# dubBoard.net
KiCad netlist of a schematic drawn in EAGLE
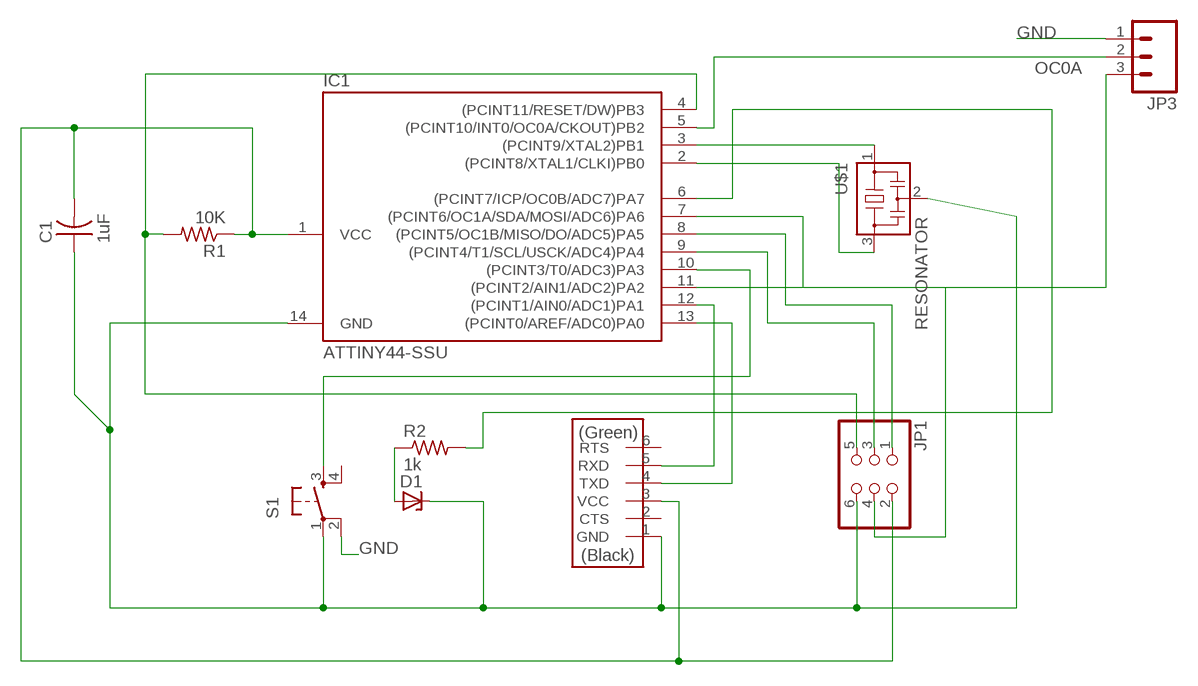
[diagram p0: schematic, sheet 1]

(export (version "E")
  (design (tool "Eeschema 10.0.6"))
  (components
    (comp (ref "C1")
      (value "1uF")
      (footprint "eagle-import:C1206FAB")
      (libsource (lib "eagle-import") (part "CAP-US1206FAB"))
    )
    (comp (ref "D1")
      (value "ZENER_DIODESOD123")
      (footprint "eagle-import:SOD123")
      (libsource (lib "eagle-import") (part "ZENER_DIODESOD123"))
    )
    (comp (ref "IC1")
      (value "ATTINY44-SSU")
      (footprint "eagle-import:SOIC14")
      (libsource (lib "eagle-import") (part "ATTINY44-SSU"))
    )
    (comp (ref "JP1")
      (value "PINHD-2X3-SMD")
      (footprint "eagle-import:2X03SMD")
      (libsource (lib "eagle-import") (part "PINHD-2X3-SMD"))
    )
    (comp (ref "JP3")
      (value "M03SMD_RA_MALE")
      (footprint "eagle-import:1X03_SMD_RA_MALE")
      (libsource (lib "eagle-import") (part "M03SMD_RA_MALE"))
    )
    (comp (ref "R1")
      (value "10K")
      (footprint "eagle-import:R1206")
      (libsource (lib "eagle-import") (part "RES-US1206"))
    )
    (comp (ref "R2")
      (value "1k")
      (footprint "eagle-import:R1206FAB")
      (libsource (lib "eagle-import") (part "RES-US1206FAB"))
    )
    (comp (ref "S1")
      (value "6MM_SWITCH6MM_SWITCH")
      (footprint "eagle-import:6MM_SWITCH")
      (libsource (lib "eagle-import") (part "6MM_SWITCH6MM_SWITCH"))
    )
    (comp (ref "U$1")
      (value "RESONATOR")
      (footprint "eagle-import:EFOBM")
      (libsource (lib "eagle-import") (part "RESONATOR"))
    )
    (comp (ref "U$2")
      (value "FTDI-SMD-HEADER")
      (footprint "eagle-import:1X06SMD")
      (libsource (lib "eagle-import") (part "FTDI-SMD-HEADER"))
    )
  )
  (nets
    (net (code "1") (name "/GND") (class "Default")
      (node (ref "C1") (pin "1") (pinfunction "1_1") (pintype "passive"))
      (node (ref "D1") (pin "CATHODE") (pinfunction "CATHODE_CATHODE") (pintype "passive"))
      (node (ref "IC1") (pin "14") (pinfunction "GND_14") (pintype "power_in"))
      (node (ref "JP1") (pin "6") (pinfunction "6_6") (pintype "passive"))
      (node (ref "JP3") (pin "1") (pinfunction "1_1") (pintype "passive"))
      (node (ref "S1") (pin "1") (pinfunction "P_1") (pintype "passive"))
      (node (ref "S1") (pin "2") (pinfunction "P1_2") (pintype "passive"))
      (node (ref "U$1") (pin "2") (pinfunction "2_2") (pintype "passive"))
      (node (ref "U$2") (pin "1") (pinfunction "GND_1") (pintype "bidirectional"))
    )
    (net (code "2") (name "/OC0A") (class "Default")
      (node (ref "IC1") (pin "5") (pinfunction "(PCINT10/INT0/OC0A/CKOUT)PB2_5") (pintype "bidirectional"))
      (node (ref "JP3") (pin "2") (pinfunction "2_2") (pintype "passive"))
    )
    (net (code "3") (name "Net-(D1-PadANODE)") (class "Default")
      (node (ref "D1") (pin "ANODE") (pinfunction "ANODE_ANODE") (pintype "passive"))
      (node (ref "R2") (pin "1") (pinfunction "1_1") (pintype "passive"))
    )
    (net (code "4") (name "Net-(IC1-(PCINT0{slash}AREF{slash}ADC0)PA0)") (class "Default")
      (node (ref "IC1") (pin "13") (pinfunction "(PCINT0/AREF/ADC0)PA0_13") (pintype "bidirectional"))
      (node (ref "U$2") (pin "4") (pinfunction "TXD_4") (pintype "bidirectional"))
    )
    (net (code "5") (name "Net-(IC1-(PCINT1{slash}AIN0{slash}ADC1)PA1)") (class "Default")
      (node (ref "IC1") (pin "12") (pinfunction "(PCINT1/AIN0/ADC1)PA1_12") (pintype "bidirectional"))
      (node (ref "U$2") (pin "5") (pinfunction "RXD_5") (pintype "bidirectional"))
    )
    (net (code "6") (name "Net-(IC1-(PCINT2{slash}AIN1{slash}ADC2)PA2)") (class "Default")
      (node (ref "IC1") (pin "11") (pinfunction "(PCINT2/AIN1/ADC2)PA2_11") (pintype "bidirectional"))
      (node (ref "JP3") (pin "3") (pinfunction "3_3") (pintype "passive"))
    )
    (net (code "7") (name "Net-(IC1-(PCINT3{slash}T0{slash}ADC3)PA3)") (class "Default")
      (node (ref "IC1") (pin "10") (pinfunction "(PCINT3/T0/ADC3)PA3_10") (pintype "bidirectional"))
      (node (ref "S1") (pin "3") (pinfunction "S_3") (pintype "passive"))
    )
    (net (code "8") (name "Net-(IC1-(PCINT4{slash}T1{slash}SCL{slash}USCK{slash}ADC4)PA4)") (class "Default")
      (node (ref "IC1") (pin "9") (pinfunction "(PCINT4/T1/SCL/USCK/ADC4)PA4_9") (pintype "bidirectional"))
      (node (ref "JP1") (pin "3") (pinfunction "3_3") (pintype "passive"))
    )
    (net (code "9") (name "Net-(IC1-(PCINT5{slash}OC1B{slash}MISO{slash}DO{slash}ADC5)PA5)") (class "Default")
      (node (ref "IC1") (pin "8") (pinfunction "(PCINT5/OC1B/MISO/DO/ADC5)PA5_8") (pintype "bidirectional"))
      (node (ref "JP1") (pin "1") (pinfunction "1_1") (pintype "passive"))
    )
    (net (code "10") (name "Net-(IC1-(PCINT6{slash}OC1A{slash}SDA{slash}MOSI{slash}ADC6)PA6)") (class "Default")
      (node (ref "IC1") (pin "7") (pinfunction "(PCINT6/OC1A/SDA/MOSI/ADC6)PA6_7") (pintype "bidirectional"))
      (node (ref "JP1") (pin "4") (pinfunction "4_4") (pintype "passive"))
    )
    (net (code "11") (name "Net-(IC1-(PCINT7{slash}ICP{slash}OC0B{slash}ADC7)PA7)") (class "Default")
      (node (ref "IC1") (pin "6") (pinfunction "(PCINT7/ICP/OC0B/ADC7)PA7_6") (pintype "bidirectional"))
      (node (ref "R2") (pin "2") (pinfunction "2_2") (pintype "passive"))
    )
    (net (code "12") (name "Net-(IC1-(PCINT8{slash}XTAL1{slash}CLKI)PB0)") (class "Default")
      (node (ref "IC1") (pin "2") (pinfunction "(PCINT8/XTAL1/CLKI)PB0_2") (pintype "bidirectional"))
      (node (ref "U$1") (pin "3") (pinfunction "3_3") (pintype "passive"))
    )
    (net (code "13") (name "Net-(IC1-(PCINT9{slash}XTAL2)PB1)") (class "Default")
      (node (ref "IC1") (pin "3") (pinfunction "(PCINT9/XTAL2)PB1_3") (pintype "bidirectional"))
      (node (ref "U$1") (pin "1") (pinfunction "1_1") (pintype "passive"))
    )
    (net (code "14") (name "Net-(IC1-(PCINT11{slash}RESET{slash}DW)PB3)") (class "Default")
      (node (ref "IC1") (pin "4") (pinfunction "(PCINT11/RESET/DW)PB3_4") (pintype "bidirectional"))
      (node (ref "JP1") (pin "5") (pinfunction "5_5") (pintype "passive"))
      (node (ref "R1") (pin "2") (pinfunction "2_2") (pintype "passive"))
    )
    (net (code "15") (name "Net-(IC1-VCC)") (class "Default")
      (node (ref "C1") (pin "2") (pinfunction "2_2") (pintype "passive"))
      (node (ref "IC1") (pin "1") (pinfunction "VCC_1") (pintype "power_in"))
      (node (ref "JP1") (pin "2") (pinfunction "2_2") (pintype "passive"))
      (node (ref "R1") (pin "1") (pinfunction "1_1") (pintype "passive"))
      (node (ref "U$2") (pin "3") (pinfunction "VCC_3") (pintype "bidirectional"))
    )
    (net (code "16") (name "unconnected-(S1-S1-Pad4)") (class "Default")
      (node (ref "S1") (pin "4") (pinfunction "S1_4") (pintype "passive"))
    )
    (net (code "17") (name "unconnected-(U$2-CTS-Pad2)") (class "Default")
      (node (ref "U$2") (pin "2") (pinfunction "CTS_2") (pintype "bidirectional"))
    )
    (net (code "18") (name "unconnected-(U$2-RTS-Pad6)") (class "Default")
      (node (ref "U$2") (pin "6") (pinfunction "RTS_6") (pintype "bidirectional"))
    )
  )
)
